# Sheet1.net
KiCad netlist of a schematic drawn in Altium Designer
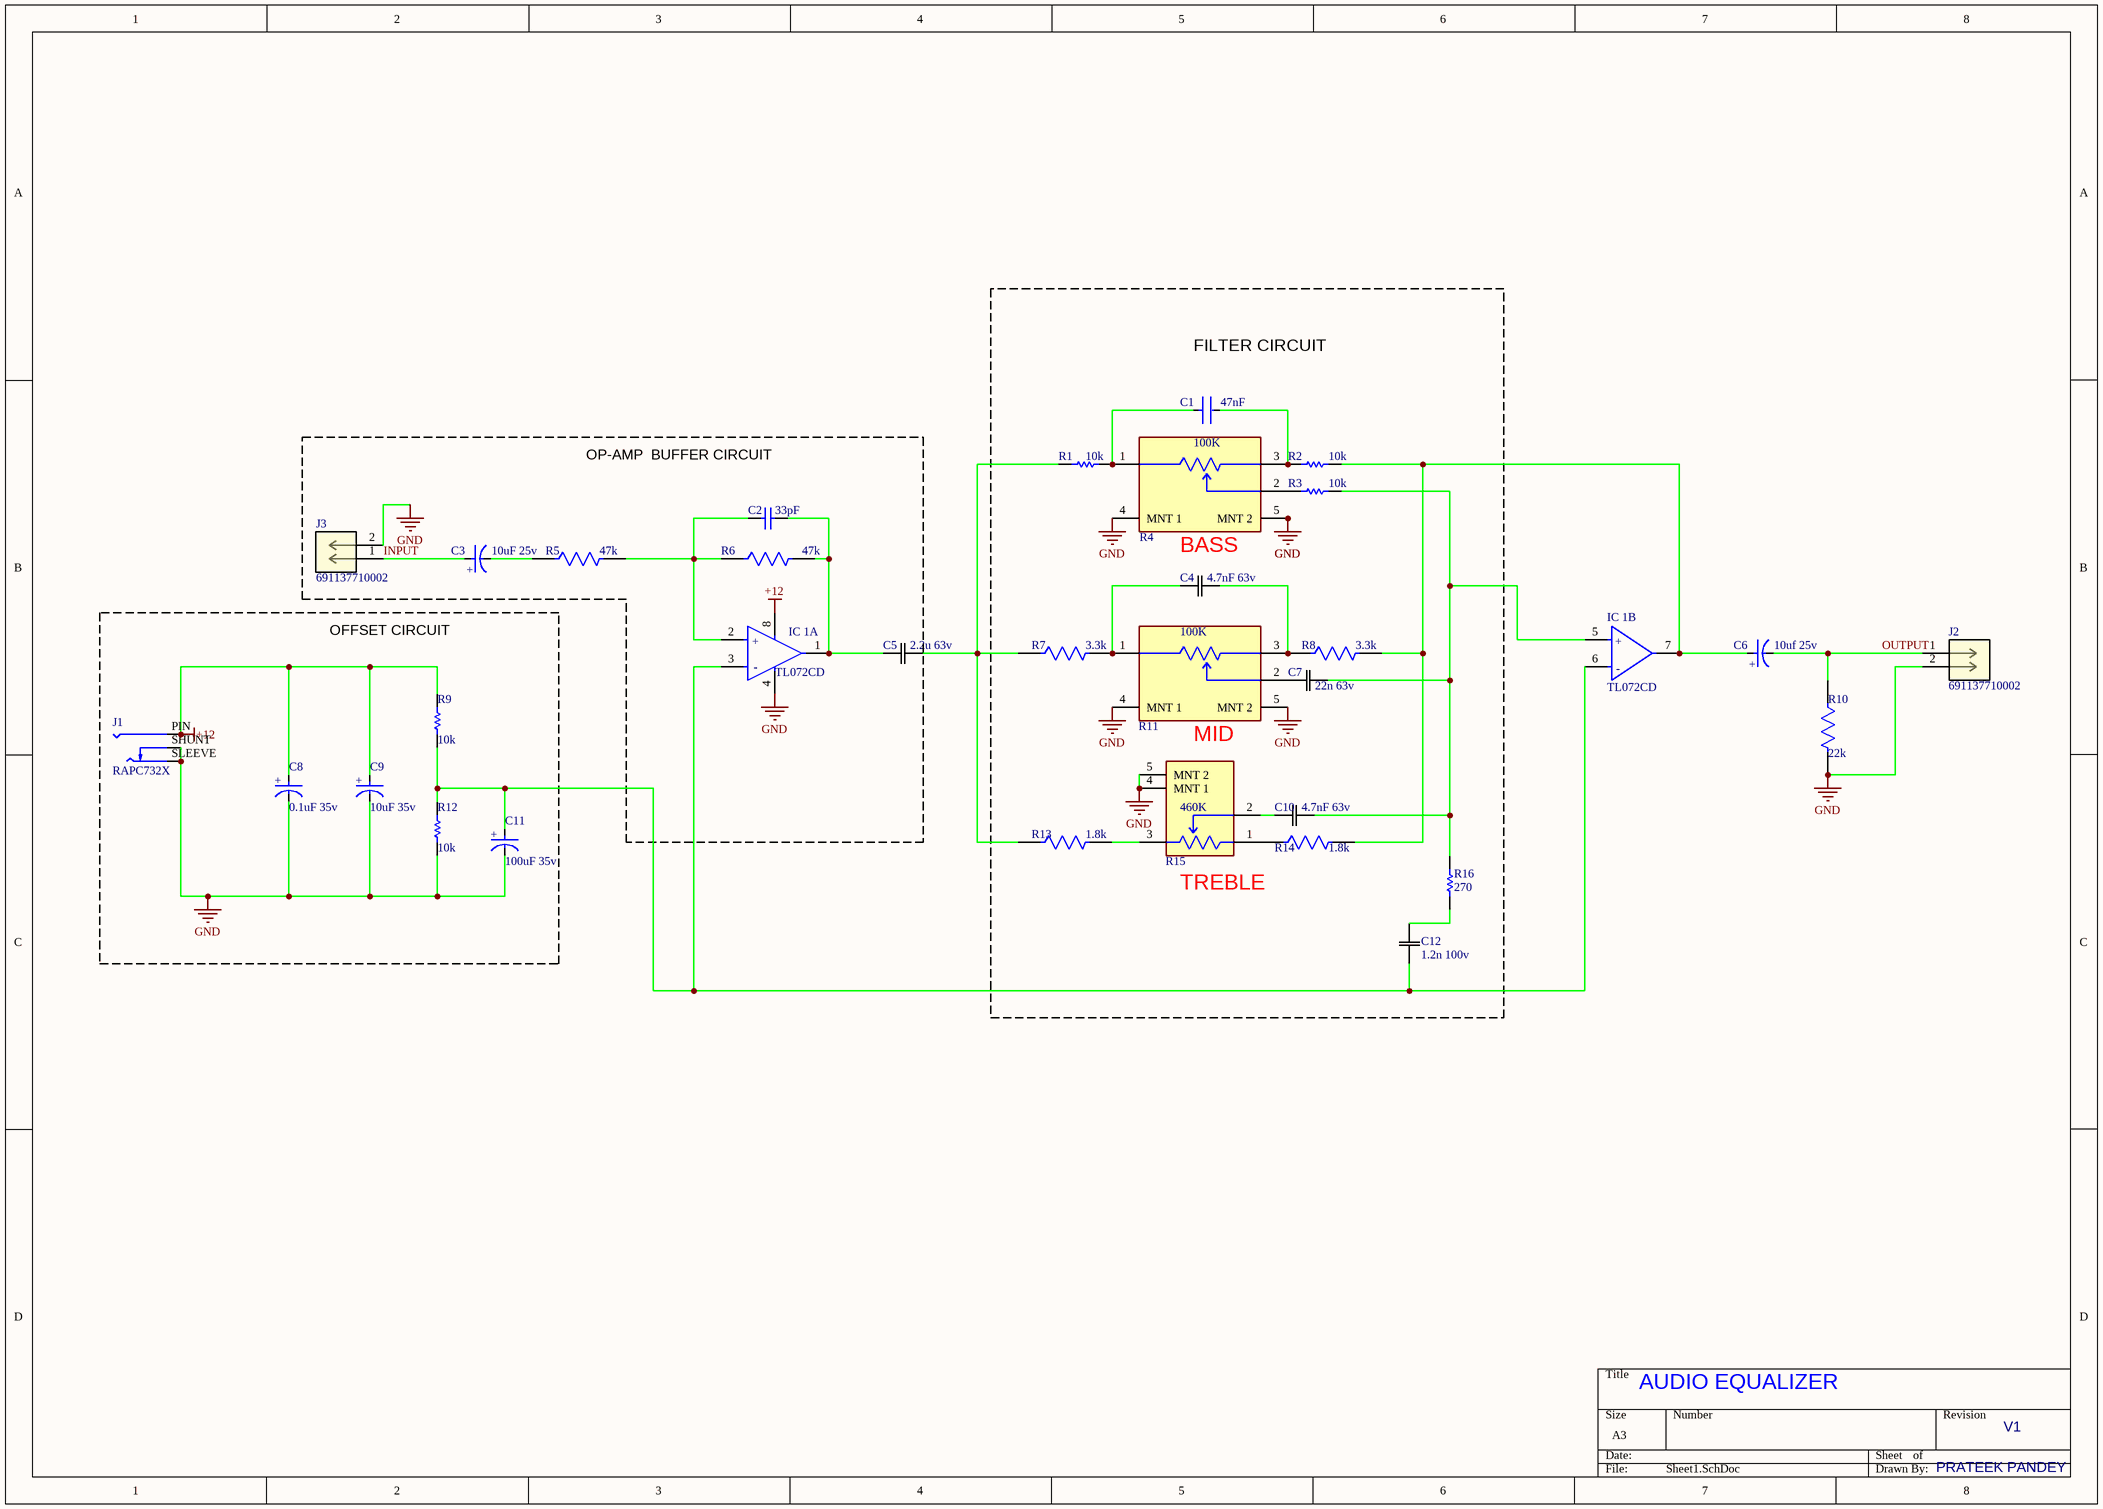
[diagram p0: Sheet1.SchDoc]

(export (version "E")
  (design (tool "Eeschema 10.0.6"))
  (components
    (comp (ref "C1")
      (value "47nF")
      (footprint "FP-0805-L_2_01_0_2-W_1_25-MFG")
      (description "General Purpose Ceramic Capacitor, 0805, 47nF, 10%, X8R, 15%, 50V")
      (fields (field (name "VOLTAGE") "50V") (field (name "TOLERANCE") "10%"))
      (libsource (lib "Altium Content Vault") (part "02cd4be3c70576c341d710602a673aa"))
    )
    (comp (ref "C2")
      (value "33pF")
      (footprint "CAPC3216X94X50ML20T25")
      (description "Chip Capacitor, 33 pF, +/- 5%, 100 V, -55 to 125 degC, 1206 (3216 Metric), RoHS, Tape and Reel")
      (fields (field (name "MANUFACTURER") "AVX"))
      (libsource (lib "Altium Content Vault") (part "CAP-NP-2"))
    )
    (comp (ref "C3")
      (value "10uF 25v")
      (footprint "FP-T491D-MFG")
      (description "CAP TANT 10UF 10% 25V 2917")
      (fields (field (name "VOLTAGE") "25V") (field (name "TOLERANCE") "20%"))
      (libsource (lib "Altium Content Vault") (part "cf48714ba7e38822c1575c7ec0b6d1f"))
    )
    (comp (ref "C4")
      (value "4.7nF 63v")
      (footprint "CAP_R82E-7P4X2P6-5P0_KEM")
      (description "No Description Available")
      (libsource (lib "R82EC1470DQ50K") (part "R82EC1470DQ50K"))
    )
    (comp (ref "C5")
      (value "2.2u 63v")
      (footprint "CAP_WCAP-ATG8_5x11_WRE")
      (description "No Description Available")
      (libsource (lib "860010772006") (part "860010772006"))
    )
    (comp (ref "C6")
      (value "10uf 25v")
      (footprint "FP-T491D-MFG")
      (description "CAP TANT 10UF 10% 25V 2917")
      (fields (field (name "VOLTAGE") "25V") (field (name "TOLERANCE") "20%"))
      (libsource (lib "Altium Content Vault") (part "cf48714ba7e38822c1575c7ec0b6d1f"))
    )
    (comp (ref "C7")
      (value "22n 63v")
      (footprint "CAP_R82_2.5X6.5X7.2_ATN")
      (description "No Description Available")
      (libsource (lib "R82EC2220DQ50J") (part "R82EC2220DQ50J"))
    )
    (comp (ref "C8")
      (value "0.1uF 35v")
      (footprint "FP-T491B105K035AT-MFG")
      (description "CAP TANT 1UF 10% 35V 1411")
      (fields (field (name "VOLTAGE") "35V") (field (name "TOLERANCE") "20%"))
      (libsource (lib "Altium Content Vault") (part "203bc49f2ac43e59fd269a8c329ed05"))
    )
    (comp (ref "C9")
      (value "10uF 35v")
      (footprint "FP-FKB-MFG")
      (description "CAP ALUM 10UF 20% 35V SMD")
      (fields (field (name "VOLTAGE") "35V") (field (name "TOLERANCE") "20%"))
      (libsource (lib "Altium Content Vault") (part "a00bbbee19879c290e62620ae7e47b1"))
    )
    (comp (ref "C10")
      (value "4.7nF 63v")
      (footprint "CAP_R82E-7P4X2P6-5P0_KEM")
      (description "No Description Available")
      (libsource (lib "R82EC1470DQ50K") (part "R82EC1470DQ50K"))
    )
    (comp (ref "C11")
      (value "100uF 35v")
      (footprint "FP-FTD-MFG")
      (description "CAP ALUM 100UF 20% 35V SMD")
      (fields (field (name "VOLTAGE") "35V") (field (name "TOLERANCE") "20%"))
      (libsource (lib "Altium Content Vault") (part "a00bbbee19879c290e62620ae7e47b1"))
    )
    (comp (ref "C12")
      (value "1.2n 100v")
      (footprint "CAP_PHE_426_DJ_4100-5150_KEM")
      (description "No Description Available")
      (libsource (lib "PHE426DJ4120JR05") (part "PHE426DJ4120JR05"))
    )
    (comp (ref "IC 1")
      (value "TL072CD")
      (footprint "FP-SO8-IPC_C")
      (description "IC OPAMP JFET 2 CIRCUIT 8SO")
      (libsource (lib "Altium Content Vault") (part "78142e87b7ae7ad9e0533b2c6f3fb9c"))
    )
    (comp (ref "J1")
      (value "RAPC732X")
      (footprint "SWITCHCRAFT_RAPC732X")
      (description "Power Barrel Connector Jack 2.50mm ID (0.098\"), 5.50mm OD (0.217\") Through Hole, Right Angle")
      (libsource (lib "RAPC732X") (part "RAPC732X"))
    )
    (comp (ref "J2")
      (value "691137710002")
      (footprint "CONN2_710002_WRE")
      (description "No Description Available")
      (libsource (lib "") (part "691137710002_1"))
    )
    (comp (ref "J3")
      (value "691137710002")
      (footprint "CONN2_710002_WRE")
      (description "No Description Available")
      (libsource (lib "691137710002") (part "691137710002"))
    )
    (comp (ref "R1")
      (value "10k")
      (footprint "RESC1609X50X30ML8T20")
      (description "Chip Resistor, 10 KOhm, +/- 1%, 100 mW, -55 to 155 degC, 0603 (1608 Metric), RoHS, Tape and Reel")
      (fields (field (name "MANUFACTURER") "Vishay Semiconductor"))
      (libsource (lib "Altium Content Vault") (part "RES-2"))
    )
    (comp (ref "R2")
      (value "10k")
      (footprint "RESC1609X50X30ML8T20")
      (description "Chip Resistor, 10 KOhm, +/- 1%, 100 mW, -55 to 155 degC, 0603 (1608 Metric), RoHS, Tape and Reel")
      (fields (field (name "MANUFACTURER") "Vishay Semiconductor"))
      (libsource (lib "Altium Content Vault") (part "RES-2"))
    )
    (comp (ref "R3")
      (value "10k")
      (footprint "RESC1609X50X30ML8T20")
      (description "Chip Resistor, 10 KOhm, +/- 1%, 100 mW, -55 to 155 degC, 0603 (1608 Metric), RoHS, Tape and Reel")
      (fields (field (name "MANUFACTURER") "Vishay Semiconductor"))
      (libsource (lib "Altium Content Vault") (part "RES-2"))
    )
    (comp (ref "R4")
      (value "P0915N-FC15BR100K")
      (footprint "Res_BI_Technologies_P0915N-FC15BR100K_eec_MFG:BI_Technologies_0_MFG")
      (libsource (lib "Res_BI_Technologies_P0915N-FC15BR100K_eec") (part "P0915N-FC15BR100K"))
    )
    (comp (ref "R5")
      (value "47k")
      (footprint "FP-CRCW0603-e3-IPC_A")
      (description "RES SMD 47K OHM 1% 1/10W 0603")
      (fields (field (name "TOLERANCE") "1%"))
      (libsource (lib "Altium Content Vault") (part "1029c3af85768c4190bb7ad29bc67b5"))
    )
    (comp (ref "R6")
      (value "47k")
      (footprint "FP-CRCW0603-e3-IPC_A")
      (description "RES SMD 47K OHM 1% 1/10W 0603")
      (fields (field (name "TOLERANCE") "1%"))
      (libsource (lib "Altium Content Vault") (part "1029c3af85768c4190bb7ad29bc67b5"))
    )
    (comp (ref "R7")
      (value "3.3k")
      (footprint "FP-CRCW0603-e3-IPC_A")
      (description "RES Thick Film, 3.3kΩ, 1%, 0.1W, 100ppm/°C, 0603")
      (fields (field (name "TOLERANCE") "1%"))
      (libsource (lib "Altium Content Vault") (part "1029c3af85768c4190bb7ad29bc67b5"))
    )
    (comp (ref "R8")
      (value "3.3k")
      (footprint "FP-CRCW0603-e3-IPC_A")
      (description "RES Thick Film, 3.3kΩ, 1%, 0.1W, 100ppm/°C, 0603")
      (fields (field (name "TOLERANCE") "1%"))
      (libsource (lib "Altium Content Vault") (part "1029c3af85768c4190bb7ad29bc67b5"))
    )
    (comp (ref "R9")
      (value "10k")
      (footprint "RESC1609X50X30ML8T20")
      (description "Chip Resistor, 10 KOhm, +/- 1%, 100 mW, -55 to 155 degC, 0603 (1608 Metric), RoHS, Tape and Reel")
      (fields (field (name "MANUFACTURER") "Vishay Semiconductor"))
      (libsource (lib "Altium Content Vault") (part "RES-2"))
    )
    (comp (ref "R10")
      (value "22k")
      (footprint "FP-ERA3A-MFG")
      (description "RES SMD 22K OHM 0.1% 1/10W 0603")
      (fields (field (name "TOLERANCE") "0.1%"))
      (libsource (lib "Altium Content Vault") (part "1029c3af85768c4190bb7ad29bc67b5"))
    )
    (comp (ref "R11")
      (value "P0915N-FC15BR100K")
      (footprint "Res_BI_Technologies_P0915N-FC15BR100K_eec_MFG:BI_Technologies_0_MFG")
      (libsource (lib "Res_BI_Technologies_P0915N-FC15BR100K_eec") (part "P0915N-FC15BR100K"))
    )
    (comp (ref "R12")
      (value "10k")
      (footprint "RESC1609X50X30ML8T20")
      (description "Chip Resistor, 10 KOhm, +/- 1%, 100 mW, -55 to 155 degC, 0603 (1608 Metric), RoHS, Tape and Reel")
      (fields (field (name "MANUFACTURER") "Vishay Semiconductor"))
      (libsource (lib "Altium Content Vault") (part "RES-2"))
    )
    (comp (ref "R13")
      (value "1.8k")
      (footprint "FP-CRCW0603-e3-IPC_A")
      (description "RES Thick Film, 1.8kΩ, 1%, 0.1W, 100ppm/°C, 0603")
      (fields (field (name "TOLERANCE") "1%"))
      (libsource (lib "Altium Content Vault") (part "1029c3af85768c4190bb7ad29bc67b5"))
    )
    (comp (ref "R14")
      (value "1.8k")
      (footprint "FP-CRCW0603-e3-IPC_A")
      (description "RES Thick Film, 1.8kΩ, 1%, 0.1W, 100ppm/°C, 0603")
      (fields (field (name "TOLERANCE") "1%"))
      (libsource (lib "Altium Content Vault") (part "1029c3af85768c4190bb7ad29bc67b5"))
    )
    (comp (ref "R15")
      (value "PTV09A-4020F-A504")
      (footprint "Res_Bourns_PTV09A-4020F-A504_eec_MFG:Bourns_0_MFG")
      (libsource (lib "Res_Bourns_PTV09A-4020F-A504_eec") (part "PTV09A-4020F-A504"))
    )
    (comp (ref "R16")
      (value "270")
      (footprint "RESC1608X55X30LL15T15")
      (fields (field (name "MANUFACTURER") "Panasonic") (field (name "PART NUMBER") "ERJ3EKF2700V"))
      (libsource (lib "Altium Content Vault") (part "RES"))
    )
  )
  (nets
    (net (code "1") (name "+12") (class "Default")
      (node (ref "C8") (pin "2") (pinfunction "A_2") (pintype "passive"))
      (node (ref "C9") (pin "2") (pinfunction "A_2") (pintype "passive"))
      (node (ref "IC 1") (pin "8") (pinfunction "VCC+_8") (pintype "power_in"))
      (node (ref "J1") (pin "PIN") (pinfunction "PIN_PIN") (pintype "passive"))
      (node (ref "R9") (pin "2") (pinfunction "2_2") (pintype "passive"))
    )
    (net (code "2") (name "/INPUT") (class "Default")
      (node (ref "C3") (pin "2") (pinfunction "A_2") (pintype "passive"))
      (node (ref "J3") (pin "1") (pinfunction "1_1") (pintype "passive"))
    )
    (net (code "3") (name "/OUTPUT") (class "Default")
      (node (ref "C6") (pin "1") (pinfunction "C_1") (pintype "passive"))
      (node (ref "J2") (pin "1") (pinfunction "1_1") (pintype "passive"))
      (node (ref "R10") (pin "1") (pinfunction "1_1") (pintype "passive"))
    )
    (net (code "4") (name "GND") (class "Default")
      (node (ref "C11") (pin "1") (pinfunction "C_1") (pintype "passive"))
      (node (ref "C8") (pin "1") (pinfunction "C_1") (pintype "passive"))
      (node (ref "C9") (pin "1") (pinfunction "C_1") (pintype "passive"))
      (node (ref "IC 1") (pin "4") (pinfunction "VCC-_4") (pintype "power_in"))
      (node (ref "J1") (pin "SHUNT") (pinfunction "SHUNT_SHUNT") (pintype "passive"))
      (node (ref "J1") (pin "SLEEVE") (pinfunction "SLEEVE_SLEEVE") (pintype "passive"))
      (node (ref "J2") (pin "2") (pinfunction "2_2") (pintype "passive"))
      (node (ref "J3") (pin "2") (pinfunction "2_2") (pintype "passive"))
      (node (ref "R10") (pin "2") (pinfunction "2_2") (pintype "passive"))
      (node (ref "R11") (pin "4") (pinfunction "MNT_1_4") (pintype "passive"))
      (node (ref "R11") (pin "5") (pinfunction "MNT_2_5") (pintype "passive"))
      (node (ref "R12") (pin "1") (pinfunction "1_1") (pintype "passive"))
      (node (ref "R15") (pin "4") (pinfunction "MNT_1_4") (pintype "passive"))
      (node (ref "R15") (pin "5") (pinfunction "MNT_2_5") (pintype "passive"))
      (node (ref "R4") (pin "4") (pinfunction "MNT_1_4") (pintype "passive"))
      (node (ref "R4") (pin "5") (pinfunction "MNT_2_5") (pintype "passive"))
    )
    (net (code "5") (name "Net-(C1-Pad1)") (class "Default")
      (node (ref "C1") (pin "1") (pinfunction "1_1") (pintype "passive"))
      (node (ref "R1") (pin "2") (pinfunction "2_2") (pintype "passive"))
      (node (ref "R4") (pin "1") (pinfunction "1_1") (pintype "passive"))
    )
    (net (code "6") (name "Net-(C1-Pad2)") (class "Default")
      (node (ref "C1") (pin "2") (pinfunction "2_2") (pintype "passive"))
      (node (ref "R2") (pin "1") (pinfunction "1_1") (pintype "passive"))
      (node (ref "R4") (pin "3") (pinfunction "3_3") (pintype "passive"))
    )
    (net (code "7") (name "Net-(C3-C)") (class "Default")
      (node (ref "C3") (pin "1") (pinfunction "C_1") (pintype "passive"))
      (node (ref "R5") (pin "1") (pinfunction "1_1") (pintype "passive"))
    )
    (net (code "8") (name "Net-(C4-Pad1)") (class "Default")
      (node (ref "C4") (pin "1") (pinfunction "1_1") (pintype "passive"))
      (node (ref "R11") (pin "1") (pinfunction "1_1") (pintype "passive"))
      (node (ref "R7") (pin "2") (pinfunction "2_2") (pintype "passive"))
    )
    (net (code "9") (name "Net-(C4-Pad2)") (class "Default")
      (node (ref "C4") (pin "2") (pinfunction "2_2") (pintype "passive"))
      (node (ref "R11") (pin "3") (pinfunction "3_3") (pintype "passive"))
      (node (ref "R8") (pin "1") (pinfunction "1_1") (pintype "passive"))
    )
    (net (code "10") (name "Net-(C5-Pad2)") (class "Default")
      (node (ref "C5") (pin "2") (pinfunction "2_2") (pintype "passive"))
      (node (ref "R1") (pin "1") (pinfunction "1_1") (pintype "passive"))
      (node (ref "R13") (pin "1") (pinfunction "1_1") (pintype "passive"))
      (node (ref "R7") (pin "1") (pinfunction "1_1") (pintype "passive"))
    )
    (net (code "11") (name "Net-(C6-A)") (class "Default")
      (node (ref "C6") (pin "2") (pinfunction "A_2") (pintype "passive"))
      (node (ref "IC 1") (pin "7") (pinfunction "Output_2_7") (pintype "passive"))
      (node (ref "R14") (pin "2") (pinfunction "2_2") (pintype "passive"))
      (node (ref "R2") (pin "2") (pinfunction "2_2") (pintype "passive"))
      (node (ref "R8") (pin "2") (pinfunction "2_2") (pintype "passive"))
    )
    (net (code "12") (name "Net-(C7-Pad2)") (class "Default")
      (node (ref "C7") (pin "2") (pinfunction "2_2") (pintype "passive"))
      (node (ref "R11") (pin "2") (pinfunction "2_2") (pintype "passive"))
    )
    (net (code "13") (name "Net-(C10-Pad1)") (class "Default")
      (node (ref "C10") (pin "1") (pinfunction "1_1") (pintype "passive"))
      (node (ref "R15") (pin "2") (pinfunction "2_2") (pintype "passive"))
    )
    (net (code "14") (name "Net-(C11-A)") (class "Default")
      (node (ref "C11") (pin "2") (pinfunction "A_2") (pintype "passive"))
      (node (ref "C12") (pin "1") (pinfunction "1_1") (pintype "passive"))
      (node (ref "IC 1") (pin "3") (pinfunction "Non-inverting_input_1_3") (pintype "tri_state"))
      (node (ref "IC 1") (pin "6") (pinfunction "Inverting_input_2_6") (pintype "tri_state"))
      (node (ref "R12") (pin "2") (pinfunction "2_2") (pintype "passive"))
      (node (ref "R9") (pin "1") (pinfunction "1_1") (pintype "passive"))
    )
    (net (code "15") (name "Net-(C12-Pad2)") (class "Default")
      (node (ref "C12") (pin "2") (pinfunction "2_2") (pintype "passive"))
      (node (ref "R16") (pin "1") (pinfunction "1_1") (pintype "passive"))
    )
    (net (code "16") (name "Net-(IC 1A-Inverting_input_1)") (class "Default")
      (node (ref "C2") (pin "1") (pinfunction "1_1") (pintype "passive"))
      (node (ref "IC 1") (pin "2") (pinfunction "Inverting_input_1_2") (pintype "tri_state"))
      (node (ref "R5") (pin "2") (pinfunction "2_2") (pintype "passive"))
      (node (ref "R6") (pin "1") (pinfunction "1_1") (pintype "passive"))
    )
    (net (code "17") (name "Net-(IC 1A-Output_1)") (class "Default")
      (node (ref "C2") (pin "2") (pinfunction "2_2") (pintype "passive"))
      (node (ref "C5") (pin "1") (pinfunction "1_1") (pintype "passive"))
      (node (ref "IC 1") (pin "1") (pinfunction "Output_1_1") (pintype "passive"))
      (node (ref "R6") (pin "2") (pinfunction "2_2") (pintype "passive"))
    )
    (net (code "18") (name "Net-(IC 1B-Non-inverting_input_2)") (class "Default")
      (node (ref "C10") (pin "2") (pinfunction "2_2") (pintype "passive"))
      (node (ref "C7") (pin "1") (pinfunction "1_1") (pintype "passive"))
      (node (ref "IC 1") (pin "5") (pinfunction "Non-inverting_input_2_5") (pintype "tri_state"))
      (node (ref "R16") (pin "2") (pinfunction "2_2") (pintype "passive"))
      (node (ref "R3") (pin "2") (pinfunction "2_2") (pintype "passive"))
    )
    (net (code "19") (name "Net-(R3-Pad1)") (class "Default")
      (node (ref "R3") (pin "1") (pinfunction "1_1") (pintype "passive"))
      (node (ref "R4") (pin "2") (pinfunction "2_2") (pintype "passive"))
    )
    (net (code "20") (name "Net-(R13-Pad2)") (class "Default")
      (node (ref "R13") (pin "2") (pinfunction "2_2") (pintype "passive"))
      (node (ref "R15") (pin "3") (pinfunction "3_3") (pintype "passive"))
    )
    (net (code "21") (name "Net-(R14-Pad1)") (class "Default")
      (node (ref "R14") (pin "1") (pinfunction "1_1") (pintype "passive"))
      (node (ref "R15") (pin "1") (pinfunction "1_1") (pintype "passive"))
    )
  )
)
